# IR.net
KiCad netlist of a schematic drawn in Altium Designer
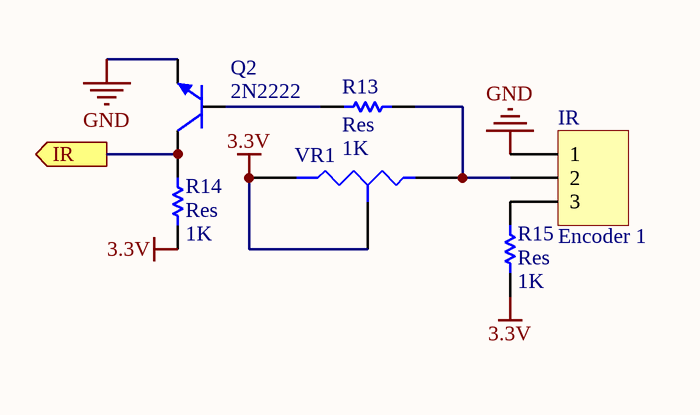
[diagram p0: IR.SchDoc]

(export (version "E")
  (design (tool "Eeschema 10.0.6"))
  (components
    (comp (ref "IR")
      (value "Encoder 1")
      (footprint "HDR1X3")
      (description "Header, 3-Pin")
      (fields (field (name "PUBLISHER") "Altium Limited"))
      (libsource (lib "KN2CLib") (part "Header 3"))
    )
    (comp (ref "Q2")
      (value "2N2222")
      (footprint "SOT-23")
      (description "NPN Bipolar Transistor")
      (fields (field (name "PUBLISHER") "Altium Limited"))
      (libsource (lib "KN2CLib") (part "2N2222"))
    )
    (comp (ref "R13")
      (value "Res")
      (footprint "2012[0805]")
      (description "Semiconductor Resistor")
      (fields (field (name "ALTIUM_VALUE") "1K") (field (name "PUBLISHER") "Altium Limited"))
      (libsource (lib "KN2CLib") (part "Res"))
    )
    (comp (ref "R14")
      (value "Res")
      (footprint "2012[0805]")
      (description "Semiconductor Resistor")
      (fields (field (name "ALTIUM_VALUE") "1K") (field (name "PUBLISHER") "Altium Limited"))
      (libsource (lib "KN2CLib") (part "Res"))
    )
    (comp (ref "R15")
      (value "Res")
      (footprint "2012[0805]")
      (description "Semiconductor Resistor")
      (fields (field (name "ALTIUM_VALUE") "1K") (field (name "PUBLISHER") "Altium Limited"))
      (libsource (lib "KN2CLib") (part "Res"))
    )
    (comp (ref "VR1")
      (value "Res Tap")
      (footprint "MULTITURN")
      (description "Tapped Resistor")
      (fields (field (name "PUBLISHER") "Altium Limited"))
      (libsource (lib "KN2CLib") (part "Res Tap"))
    )
  )
  (nets
    (net (code "1") (name "/IR") (class "Default")
      (node (ref "Q2") (pin "1") (pinfunction "C_1") (pintype "passive"))
      (node (ref "R14") (pin "2") (pinfunction "2_2") (pintype "passive"))
    )
    (net (code "2") (name "3.3V") (class "Default")
      (node (ref "R14") (pin "1") (pinfunction "1_1") (pintype "passive"))
      (node (ref "R15") (pin "1") (pinfunction "1_1") (pintype "passive"))
      (node (ref "VR1") (pin "2") (pinfunction "B_2") (pintype "passive"))
      (node (ref "VR1") (pin "3") (pinfunction "TAP_3") (pintype "passive"))
    )
    (net (code "3") (name "GND") (class "Default")
      (node (ref "IR") (pin "1") (pinfunction "1_1") (pintype "passive"))
      (node (ref "Q2") (pin "3") (pinfunction "E_3") (pintype "passive"))
    )
    (net (code "4") (name "Net-(IR-Pad3)") (class "Default")
      (node (ref "IR") (pin "3") (pinfunction "3_3") (pintype "passive"))
      (node (ref "R15") (pin "2") (pinfunction "2_2") (pintype "passive"))
    )
    (net (code "5") (name "Net-(Q2-B)") (class "Default")
      (node (ref "Q2") (pin "2") (pinfunction "B_2") (pintype "passive"))
      (node (ref "R13") (pin "1") (pinfunction "1_1") (pintype "passive"))
    )
    (net (code "6") (name "Net-(VR1-A)") (class "Default")
      (node (ref "IR") (pin "2") (pinfunction "2_2") (pintype "passive"))
      (node (ref "R13") (pin "2") (pinfunction "2_2") (pintype "passive"))
      (node (ref "VR1") (pin "1") (pinfunction "A_1") (pintype "passive"))
    )
  )
)
